# PROC106B_AOP_IO.net
KiCad netlist of a schematic drawn in Altium Designer
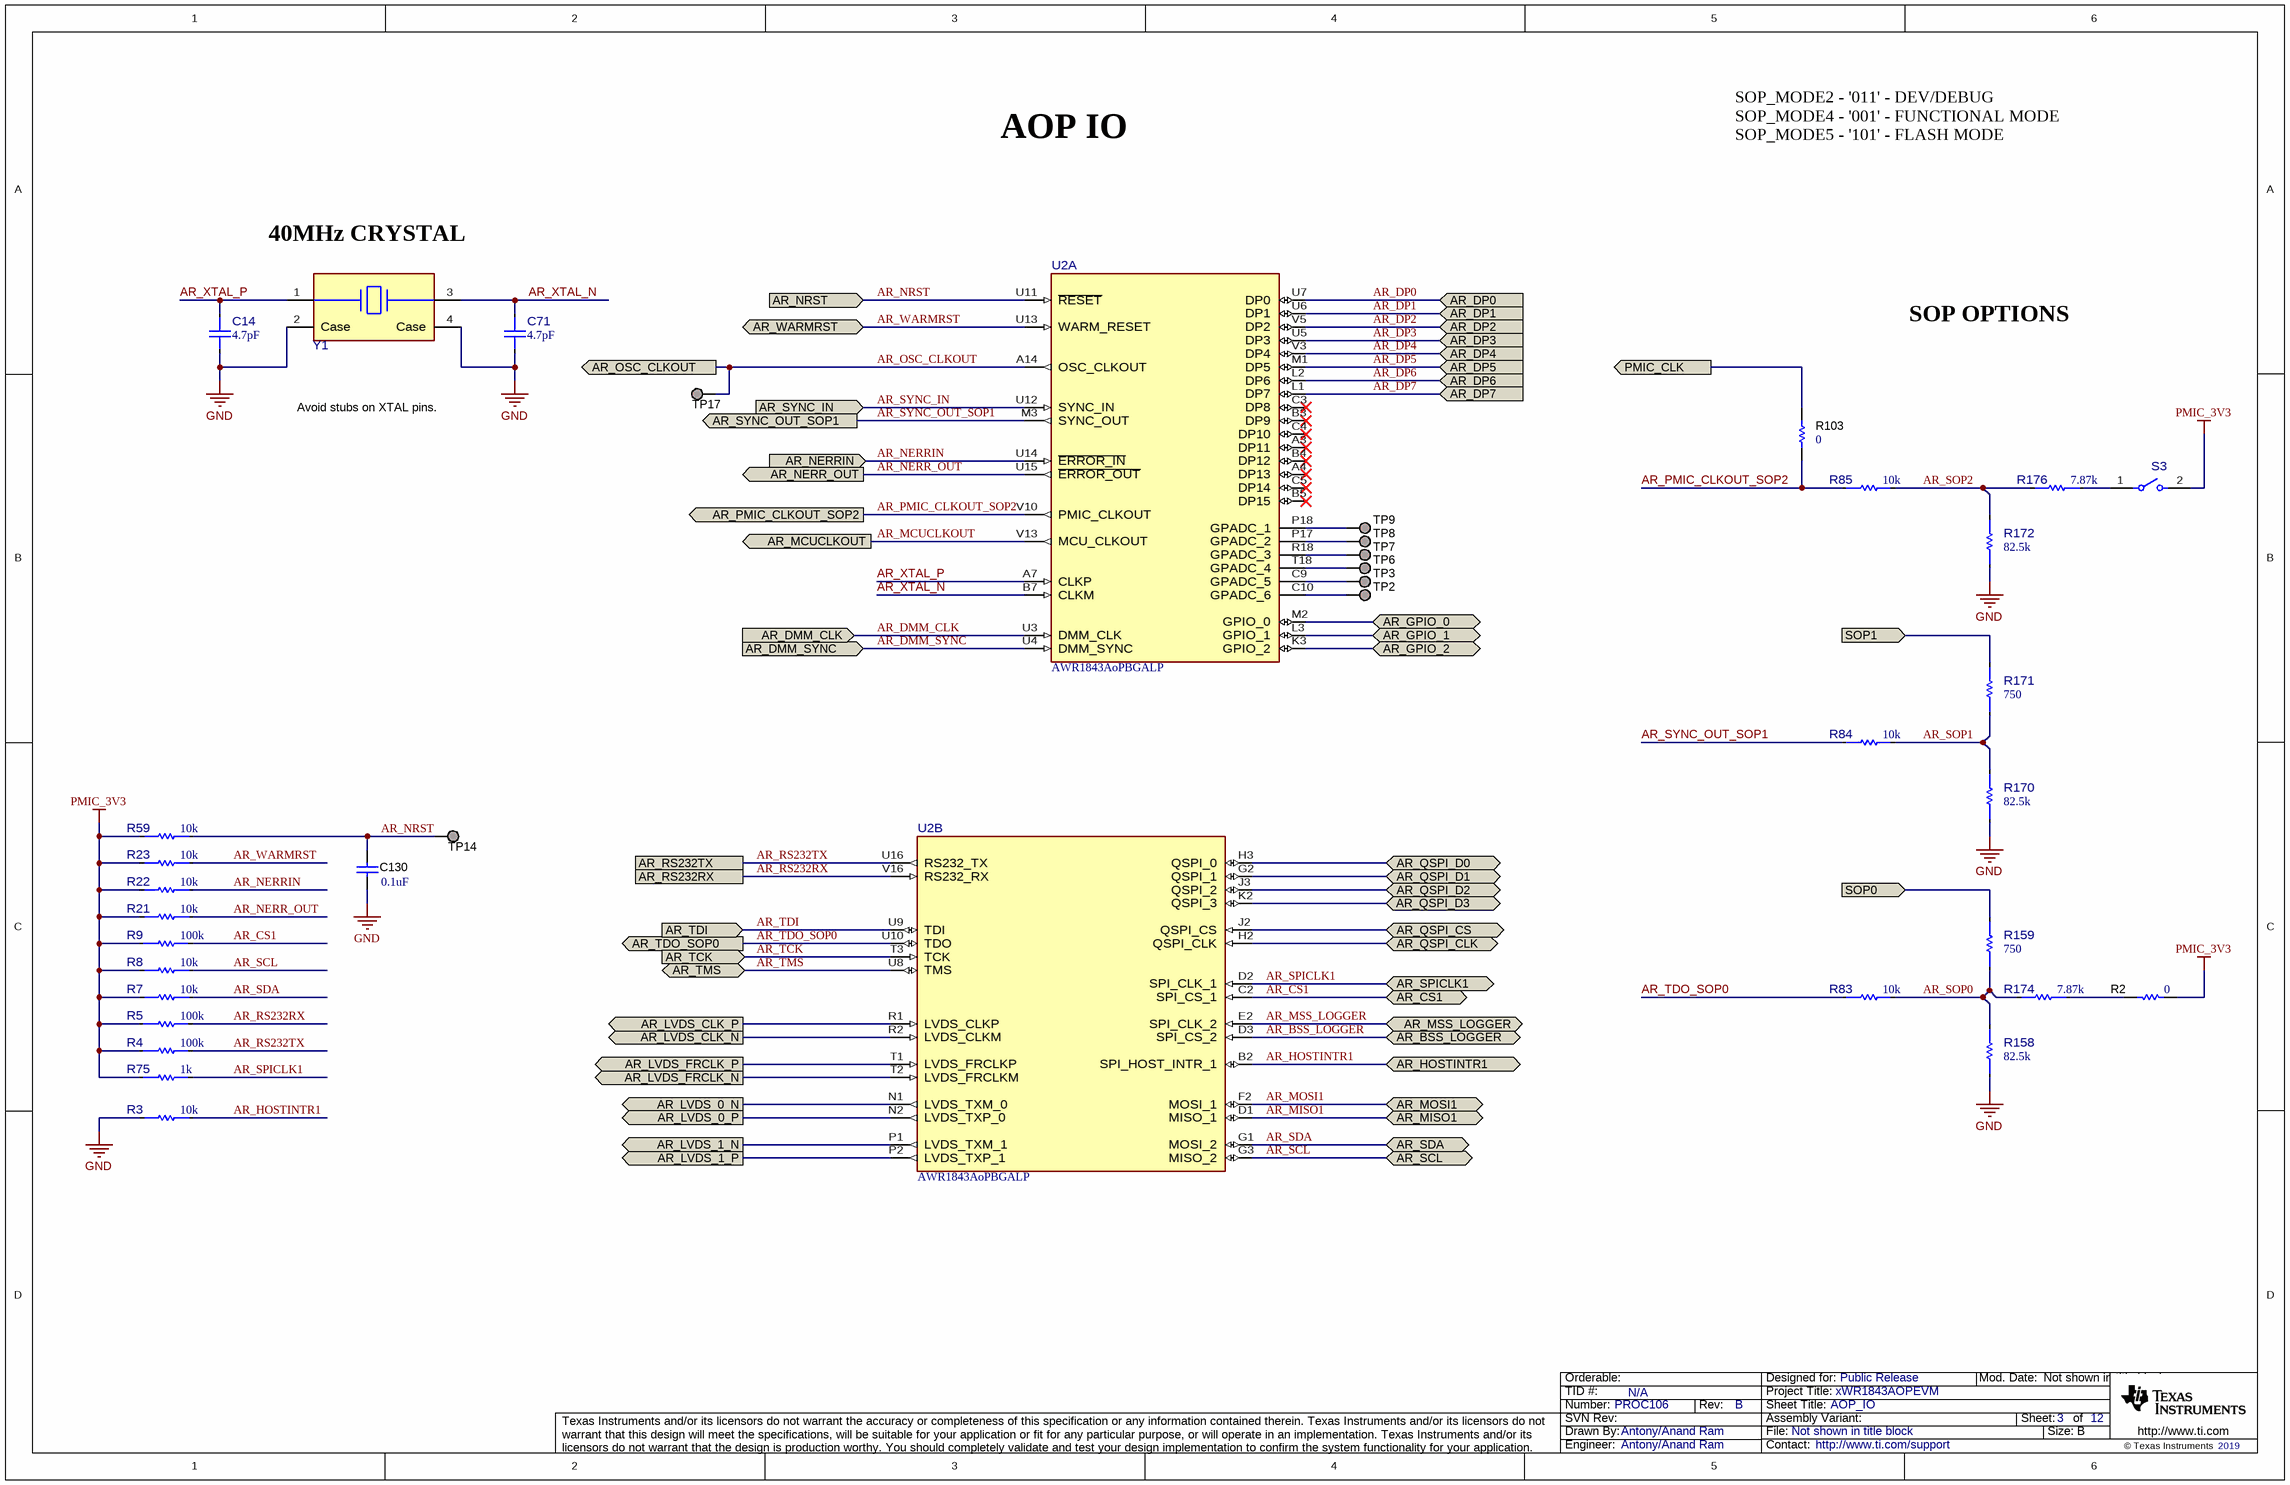
[diagram p0: PROC106B_AOP_IO.SchDoc]

(export (version "E")
  (design (tool "Eeschema 10.0.6"))
  (components
    (comp (ref "C14")
      (value "CGA1A2C0G1H4R7C030BA")
      (footprint "FP-CGA1A2C0G1H4R7C030BA_0201-IPC_C")
      (description "Cap Ceramic 4.7pF 50V C0G 0.25pF Pad SMD 0201 125°C Automotive T/R")
      (fields (field (name "MANUFACTURER") "TDK") (field (name "VALUEDISPLAYED") "4.7pF"))
      (libsource (lib "Altium Vault - TI") (part "SYM-CGA1A2C0G1H4R7C030BA"))
    )
    (comp (ref "C71")
      (value "CGA1A2C0G1H4R7C030BA")
      (footprint "FP-CGA1A2C0G1H4R7C030BA_0201-IPC_C")
      (description "Cap Ceramic 4.7pF 50V C0G 0.25pF Pad SMD 0201 125°C Automotive T/R")
      (fields (field (name "MANUFACTURER") "TDK") (field (name "VALUEDISPLAYED") "4.7pF"))
      (libsource (lib "Altium Vault - TI") (part "SYM-CGA1A2C0G1H4R7C030BA"))
    )
    (comp (ref "C130")
      (value "GCM155R71C104KA55D")
      (footprint "0402L")
      (description "CAP, CERM, 0.1 uF, 16 V, +/- 10%, X7R, 0402")
      (fields
        (field (name "MANUFACTURER") "MuRata")
        (field (name "VALUEDISPLAYED") "0.1uF")
        (field (name "PUBLISHER") "Texas Instruments")
      )
      (libsource (lib "Altium Vault - TI") (part "Capacitor"))
    )
    (comp (ref "R2")
      (value "ERJ-1GN0R00C")
      (footprint "0201L")
      (description "RES, 0, 5%, .05 W, AEC-Q200 Grade 0, 0201")
      (fields
        (field (name "MANUFACTURER") "Panasonic")
        (field (name "VALUEDISPLAYED") "0")
        (field (name "PUBLISHER") "Texas Instruments")
      )
      (libsource (lib "Altium Vault - TI") (part "Resistor"))
    )
    (comp (ref "R3")
      (value "10k")
      (footprint "FP-ERA-1AEB103C_0201-IPC_C")
      (description "RES SMD 10K OHM 0.1% 1/20W 0201")
      (fields (field (name "MANUFACTURER") "Panasonic") (field (name "PARTNUMBER") "ERA-1AEB103C"))
      (libsource (lib "Altium Vault - TI") (part "SYM-ERA-1AEB103C"))
    )
    (comp (ref "R4")
      (value "100k")
      (footprint "FP-ERJ-1GNF1003C_0201-IPC_C")
      (description "100 kOhms ±1% 0.05W, 1/20W Chip Resistor 0201 (0603 Metric) Automotive AEC-Q200 Thick Film")
      (fields
        (field (name "MANUFACTURER") "Panasonic Electronic Components")
        (field (name "PARTNUMBER") "ERJ-1GNF1003C")
      )
      (libsource (lib "Altium Vault - TI") (part "SYM-ERJ-1GNF1003C"))
    )
    (comp (ref "R5")
      (value "100k")
      (footprint "FP-ERJ-1GNF1003C_0201-IPC_C")
      (description "100 kOhms ±1% 0.05W, 1/20W Chip Resistor 0201 (0603 Metric) Automotive AEC-Q200 Thick Film")
      (fields
        (field (name "MANUFACTURER") "Panasonic Electronic Components")
        (field (name "PARTNUMBER") "ERJ-1GNF1003C")
      )
      (libsource (lib "Altium Vault - TI") (part "SYM-ERJ-1GNF1003C"))
    )
    (comp (ref "R7")
      (value "10k")
      (footprint "FP-ERA-1AEB103C_0201-IPC_C")
      (description "RES SMD 10K OHM 0.1% 1/20W 0201")
      (fields (field (name "MANUFACTURER") "Panasonic") (field (name "PARTNUMBER") "ERA-1AEB103C"))
      (libsource (lib "Altium Vault - TI") (part "SYM-ERA-1AEB103C"))
    )
    (comp (ref "R8")
      (value "10k")
      (footprint "FP-ERA-1AEB103C_0201-IPC_C")
      (description "RES SMD 10K OHM 0.1% 1/20W 0201")
      (fields (field (name "MANUFACTURER") "Panasonic") (field (name "PARTNUMBER") "ERA-1AEB103C"))
      (libsource (lib "Altium Vault - TI") (part "SYM-ERA-1AEB103C"))
    )
    (comp (ref "R9")
      (value "100k")
      (footprint "FP-ERJ-1GNF1003C_0201-IPC_C")
      (description "100 kOhms ±1% 0.05W, 1/20W Chip Resistor 0201 (0603 Metric) Automotive AEC-Q200 Thick Film")
      (fields
        (field (name "MANUFACTURER") "Panasonic Electronic Components")
        (field (name "PARTNUMBER") "ERJ-1GNF1003C")
      )
      (libsource (lib "Altium Vault - TI") (part "SYM-ERJ-1GNF1003C"))
    )
    (comp (ref "R21")
      (value "10k")
      (footprint "FP-ERA-1AEB103C_0201-IPC_C")
      (description "RES SMD 10K OHM 0.1% 1/20W 0201")
      (fields (field (name "MANUFACTURER") "Panasonic") (field (name "PARTNUMBER") "ERA-1AEB103C"))
      (libsource (lib "Altium Vault - TI") (part "SYM-ERA-1AEB103C"))
    )
    (comp (ref "R22")
      (value "10k")
      (footprint "FP-ERA-1AEB103C_0201-IPC_C")
      (description "RES SMD 10K OHM 0.1% 1/20W 0201")
      (fields (field (name "MANUFACTURER") "Panasonic") (field (name "PARTNUMBER") "ERA-1AEB103C"))
      (libsource (lib "Altium Vault - TI") (part "SYM-ERA-1AEB103C"))
    )
    (comp (ref "R23")
      (value "10k")
      (footprint "FP-ERA-1AEB103C_0201-IPC_C")
      (description "RES SMD 10K OHM 0.1% 1/20W 0201")
      (fields (field (name "MANUFACTURER") "Panasonic") (field (name "PARTNUMBER") "ERA-1AEB103C"))
      (libsource (lib "Altium Vault - TI") (part "SYM-ERA-1AEB103C"))
    )
    (comp (ref "R59")
      (value "10k")
      (footprint "FP-ERA-1AEB103C_0201-IPC_C")
      (description "RES SMD 10K OHM 0.1% 1/20W 0201")
      (fields (field (name "MANUFACTURER") "Panasonic") (field (name "PARTNUMBER") "ERA-1AEB103C"))
      (libsource (lib "Altium Vault - TI") (part "SYM-ERA-1AEB103C"))
    )
    (comp (ref "R75")
      (value "1k")
      (footprint "FP-ERJ-1GNJ102C_0201-IPC_C")
      (description "1 kOhms ±5% 0.05W, 1/20W Chip Resistor 0201 (0603 Metric) Automotive AEC-Q200 Thick Film")
      (fields
        (field (name "MANUFACTURER") "Panasonic Electronic Components")
        (field (name "PARTNUMBER") "ERJ-1GNJ102C")
      )
      (libsource (lib "Altium Vault - TI") (part "SYM-ERJ-1GNJ102C"))
    )
    (comp (ref "R83")
      (value "10k")
      (footprint "FP-ERA-1AEB103C_0201-IPC_C")
      (description "RES SMD 10K OHM 0.1% 1/20W 0201")
      (fields (field (name "MANUFACTURER") "Panasonic") (field (name "PARTNUMBER") "ERA-1AEB103C"))
      (libsource (lib "Altium Vault - TI") (part "SYM-ERA-1AEB103C"))
    )
    (comp (ref "R84")
      (value "10k")
      (footprint "FP-ERA-1AEB103C_0201-IPC_C")
      (description "RES SMD 10K OHM 0.1% 1/20W 0201")
      (fields (field (name "MANUFACTURER") "Panasonic") (field (name "PARTNUMBER") "ERA-1AEB103C"))
      (libsource (lib "Altium Vault - TI") (part "SYM-ERA-1AEB103C"))
    )
    (comp (ref "R85")
      (value "10k")
      (footprint "FP-ERA-1AEB103C_0201-IPC_C")
      (description "RES SMD 10K OHM 0.1% 1/20W 0201")
      (fields (field (name "MANUFACTURER") "Panasonic") (field (name "PARTNUMBER") "ERA-1AEB103C"))
      (libsource (lib "Altium Vault - TI") (part "SYM-ERA-1AEB103C"))
    )
    (comp (ref "R103")
      (value "ERJ-1GN0R00C")
      (footprint "0201L")
      (description "RES, 0, 5%, .05 W, AEC-Q200 Grade 0, 0201")
      (fields
        (field (name "MANUFACTURER") "Panasonic")
        (field (name "VALUEDISPLAYED") "0")
        (field (name "PUBLISHER") "Texas Instruments")
      )
      (libsource (lib "Altium Vault - TI") (part "Resistor"))
    )
    (comp (ref "R158")
      (value "82.5k")
      (footprint "FP-ERJ-1GNF8252C_0201-IPC_C")
      (description "Res Thick Film 0201 82.5K Ohm 1% 1/20W ±200ppm/°C Molded SMD SMD T/R")
      (fields (field (name "MANUFACTURER") "Panasonic") (field (name "PARTNUMBER") "ERJ-1GNF8252C"))
      (libsource (lib "Altium Vault - TI") (part "SYM-ERJ-1GNF8252C"))
    )
    (comp (ref "R159")
      (value "750")
      (footprint "FP-ERJ-1GNJ751C_0201-IPC_C")
      (description "Res Thick Film 0201 750 Ohm 5% 0.05W(1/20W) ±200ppm/C Pad SMD Automotive T/R")
      (fields
        (field (name "MANUFACTURER") "Panasonic Electronic Components")
        (field (name "PARTNUMBER") "ERJ-1GNJ751C")
      )
      (libsource (lib "Altium Vault - TI") (part "SYM-ERJ-1GNJ751C"))
    )
    (comp (ref "R170")
      (value "82.5k")
      (footprint "FP-ERJ-1GNF8252C_0201-IPC_C")
      (description "Res Thick Film 0201 82.5K Ohm 1% 1/20W ±200ppm/°C Molded SMD SMD T/R")
      (fields (field (name "MANUFACTURER") "Panasonic") (field (name "PARTNUMBER") "ERJ-1GNF8252C"))
      (libsource (lib "Altium Vault - TI") (part "SYM-ERJ-1GNF8252C"))
    )
    (comp (ref "R171")
      (value "750")
      (footprint "FP-ERJ-1GNJ751C_0201-IPC_C")
      (description "Res Thick Film 0201 750 Ohm 5% 0.05W(1/20W) ±200ppm/C Pad SMD Automotive T/R")
      (fields
        (field (name "MANUFACTURER") "Panasonic Electronic Components")
        (field (name "PARTNUMBER") "ERJ-1GNJ751C")
      )
      (libsource (lib "Altium Vault - TI") (part "SYM-ERJ-1GNJ751C"))
    )
    (comp (ref "R172")
      (value "82.5k")
      (footprint "FP-ERJ-1GNF8252C_0201-IPC_C")
      (description "Res Thick Film 0201 82.5K Ohm 1% 1/20W ±200ppm/°C Molded SMD SMD T/R")
      (fields (field (name "MANUFACTURER") "Panasonic") (field (name "PARTNUMBER") "ERJ-1GNF8252C"))
      (libsource (lib "Altium Vault - TI") (part "SYM-ERJ-1GNF8252C"))
    )
    (comp (ref "R174")
      (value "7.87k")
      (footprint "FP-ERJ-1GNF7871C_0201-IPC_C")
      (description "Res Thick Film 0201 7.87K Ohm 1% 1/20W ±200ppm/°C Molded SMD SMD T/R")
      (fields (field (name "MANUFACTURER") "Panasonic") (field (name "PARTNUMBER") "ERJ-1GNF7871C"))
      (libsource (lib "Altium Vault - TI") (part "SYM-ERJ-1GNF7871C"))
    )
    (comp (ref "R176")
      (value "7.87k")
      (footprint "FP-ERJ-1GNF7871C_0201-IPC_C")
      (description "Res Thick Film 0201 7.87K Ohm 1% 1/20W ±200ppm/°C Molded SMD SMD T/R")
      (fields (field (name "MANUFACTURER") "Panasonic") (field (name "PARTNUMBER") "ERJ-1GNF7871C"))
      (libsource (lib "Altium Vault - TI") (part "SYM-ERJ-1GNF7871C"))
    )
    (comp (ref "S3")
      (value "CHS-01TA")
      (footprint "FP-CHS-01TA_SMT_SW_5MM4_2MM5-MFG")
      (description "SWITCH SLIDE DIP SPST 100MA 6V")
      (fields (field (name "MANUFACTURER") "Nidec Copal Electronics"))
      (libsource (lib "Altium Vault - TI") (part "SYM-PTS635SK25SM"))
    )
    (comp (ref "TP2")
      (value "TESTPOINT")
      (footprint "TP_25MIL-SMT")
      (description "TEST POINT.  No entry in BOM.")
      (libsource (lib "Altium Vault - TI") (part "TESTPOINT"))
    )
    (comp (ref "TP3")
      (value "TESTPOINT")
      (footprint "TP_25MIL-SMT")
      (description "TEST POINT.  No entry in BOM.")
      (libsource (lib "Altium Vault - TI") (part "TESTPOINT"))
    )
    (comp (ref "TP6")
      (value "TESTPOINT")
      (footprint "TP_25MIL-SMT")
      (description "TEST POINT.  No entry in BOM.")
      (libsource (lib "Altium Vault - TI") (part "TESTPOINT"))
    )
    (comp (ref "TP7")
      (value "TESTPOINT")
      (footprint "TP_25MIL-SMT")
      (description "TEST POINT.  No entry in BOM.")
      (libsource (lib "Altium Vault - TI") (part "TESTPOINT"))
    )
    (comp (ref "TP8")
      (value "TESTPOINT")
      (footprint "TP_25MIL-SMT")
      (description "TEST POINT.  No entry in BOM.")
      (libsource (lib "Altium Vault - TI") (part "TESTPOINT"))
    )
    (comp (ref "TP9")
      (value "TESTPOINT")
      (footprint "TP_25MIL-SMT")
      (description "TEST POINT.  No entry in BOM.")
      (libsource (lib "Altium Vault - TI") (part "TESTPOINT"))
    )
    (comp (ref "TP14")
      (value "TESTPOINT")
      (footprint "TP_25MIL-SMT")
      (description "TEST POINT.  No entry in BOM.")
      (libsource (lib "Altium Vault - TI") (part "TESTPOINT"))
    )
    (comp (ref "TP17")
      (value "TESTPOINT")
      (footprint "TP_25MIL-SMT")
      (description "TEST POINT.  No entry in BOM.")
      (libsource (lib "Altium Vault - TI") (part "TESTPOINT"))
    )
    (comp (ref "U2")
      (value "AWR1843AoPBGALP")
      (footprint "ALP0180A-MFG")
      (fields (field (name "MANUFACTURER") "Texas Instruments") (field (name "PARTNUMBER") "AWR1843AoPBGALP"))
      (libsource (lib "Altium Vault - TI") (part "SYM-AWR1843AoPBGALP"))
    )
    (comp (ref "Y1")
      (value "FW4000044Q")
      (footprint "FP-FW4000044Q_4-SMD-2.0x1.6mm-MFG")
      (description "40MHz ±10ppm Crystal 8pF 50 Ohms 4-SMD, No Lead")
      (fields (field (name "MANUFACTURER") "Diodes") (field (name "DIGIKEY PART NUMBER") "FW4000044QDICT-ND"))
      (libsource (lib "Altium Vault - TI") (part "SYM-FW4000044Q"))
    )
  )
  (nets
    (net (code "1") (name "/AR_BSS_LOGGER") (class "Default")
      (node (ref "U2") (pin "D3") (pinfunction "SPI_CS_2_D3") (pintype "input"))
    )
    (net (code "2") (name "/AR_CS1") (class "Default")
      (node (ref "R9") (pin "2") (pinfunction "2_2") (pintype "passive"))
      (node (ref "U2") (pin "C2") (pinfunction "SPI_CS_1_C2") (pintype "input"))
    )
    (net (code "3") (name "/AR_DMM_CLK") (class "Default")
      (node (ref "U2") (pin "U3") (pinfunction "DMM_CLK_U3") (pintype "input"))
    )
    (net (code "4") (name "/AR_DMM_SYNC") (class "Default")
      (node (ref "U2") (pin "U4") (pinfunction "DMM_SYNC_U4") (pintype "input"))
    )
    (net (code "5") (name "/AR_DP0") (class "Default")
      (node (ref "U2") (pin "U7") (pinfunction "DP0_U7") (pintype "bidirectional"))
    )
    (net (code "6") (name "/AR_DP1") (class "Default")
      (node (ref "U2") (pin "U6") (pinfunction "DP1_U6") (pintype "bidirectional"))
    )
    (net (code "7") (name "/AR_DP2") (class "Default")
      (node (ref "U2") (pin "V5") (pinfunction "DP2_V5") (pintype "bidirectional"))
    )
    (net (code "8") (name "/AR_DP3") (class "Default")
      (node (ref "U2") (pin "U5") (pinfunction "DP3_U5") (pintype "bidirectional"))
    )
    (net (code "9") (name "/AR_DP4") (class "Default")
      (node (ref "U2") (pin "V3") (pinfunction "DP4_V3") (pintype "bidirectional"))
    )
    (net (code "10") (name "/AR_DP5") (class "Default")
      (node (ref "U2") (pin "M1") (pinfunction "DP5_M1") (pintype "bidirectional"))
    )
    (net (code "11") (name "/AR_DP6") (class "Default")
      (node (ref "U2") (pin "L2") (pinfunction "DP6_L2") (pintype "bidirectional"))
    )
    (net (code "12") (name "/AR_DP7") (class "Default")
      (node (ref "U2") (pin "L1") (pinfunction "DP7_L1") (pintype "bidirectional"))
    )
    (net (code "13") (name "/AR_GPIO_0") (class "Default")
      (node (ref "U2") (pin "M2") (pinfunction "GPIO_0_M2") (pintype "bidirectional"))
    )
    (net (code "14") (name "/AR_GPIO_1") (class "Default")
      (node (ref "U2") (pin "L3") (pinfunction "GPIO_1_L3") (pintype "bidirectional"))
    )
    (net (code "15") (name "/AR_GPIO_2") (class "Default")
      (node (ref "U2") (pin "K3") (pinfunction "GPIO_2_K3") (pintype "bidirectional"))
    )
    (net (code "16") (name "/AR_HOSTINTR1") (class "Default")
      (node (ref "R3") (pin "1") (pinfunction "1_1") (pintype "passive"))
      (node (ref "U2") (pin "B2") (pinfunction "SPI_HOST_INTR_1_B2") (pintype "bidirectional"))
    )
    (net (code "17") (name "/AR_LVDS_0_N") (class "Default")
      (node (ref "U2") (pin "N1") (pinfunction "LVDS_TXM_0_N1") (pintype "output"))
    )
    (net (code "18") (name "/AR_LVDS_0_P") (class "Default")
      (node (ref "U2") (pin "N2") (pinfunction "LVDS_TXP_0_N2") (pintype "output"))
    )
    (net (code "19") (name "/AR_LVDS_1_N") (class "Default")
      (node (ref "U2") (pin "P1") (pinfunction "LVDS_TXM_1_P1") (pintype "output"))
    )
    (net (code "20") (name "/AR_LVDS_1_P") (class "Default")
      (node (ref "U2") (pin "P2") (pinfunction "LVDS_TXP_1_P2") (pintype "output"))
    )
    (net (code "21") (name "/AR_LVDS_CLK_N") (class "Default")
      (node (ref "U2") (pin "R2") (pinfunction "LVDS_CLKM_R2") (pintype "input"))
    )
    (net (code "22") (name "/AR_LVDS_CLK_P") (class "Default")
      (node (ref "U2") (pin "R1") (pinfunction "LVDS_CLKP_R1") (pintype "input"))
    )
    (net (code "23") (name "/AR_LVDS_FRCLK_N") (class "Default")
      (node (ref "U2") (pin "T2") (pinfunction "LVDS_FRCLKM_T2") (pintype "input"))
    )
    (net (code "24") (name "/AR_LVDS_FRCLK_P") (class "Default")
      (node (ref "U2") (pin "T1") (pinfunction "LVDS_FRCLKP_T1") (pintype "input"))
    )
    (net (code "25") (name "/AR_MCUCLKOUT") (class "Default")
      (node (ref "U2") (pin "V13") (pinfunction "MCU_CLKOUT_V13") (pintype "output"))
    )
    (net (code "26") (name "/AR_MISO1") (class "Default")
      (node (ref "U2") (pin "D1") (pinfunction "MISO_1_D1") (pintype "bidirectional"))
    )
    (net (code "27") (name "/AR_MOSI1") (class "Default")
      (node (ref "U2") (pin "F2") (pinfunction "MOSI_1_F2") (pintype "bidirectional"))
    )
    (net (code "28") (name "/AR_MSS_LOGGER") (class "Default")
      (node (ref "U2") (pin "E2") (pinfunction "SPI_CLK_2_E2") (pintype "input"))
    )
    (net (code "29") (name "/AR_NERRIN") (class "Default")
      (node (ref "R22") (pin "1") (pinfunction "1_1") (pintype "passive"))
      (node (ref "U2") (pin "U14") (pinfunction "~{ERROR_IN}_U14") (pintype "input"))
    )
    (net (code "30") (name "/AR_NERR_OUT") (class "Default")
      (node (ref "R21") (pin "1") (pinfunction "1_1") (pintype "passive"))
      (node (ref "U2") (pin "U15") (pinfunction "~{ERROR_OUT}_U15") (pintype "output"))
    )
    (net (code "31") (name "/AR_NRST") (class "Default")
      (node (ref "C130") (pin "2") (pinfunction "2_2") (pintype "passive"))
      (node (ref "R59") (pin "1") (pinfunction "1_1") (pintype "passive"))
      (node (ref "TP14") (pin "1") (pintype "passive"))
      (node (ref "U2") (pin "U11") (pinfunction "~{RESET}_U11") (pintype "input"))
    )
    (net (code "32") (name "/AR_OSC_CLKOUT") (class "Default")
      (node (ref "TP17") (pin "1") (pintype "passive"))
      (node (ref "U2") (pin "A14") (pinfunction "OSC_CLKOUT_A14") (pintype "output"))
    )
    (net (code "33") (name "/AR_PMIC_CLKOUT_SOP2") (class "Default")
      (node (ref "R103") (pin "1") (pinfunction "1_1") (pintype "passive"))
      (node (ref "R85") (pin "1") (pinfunction "1_1") (pintype "passive"))
      (node (ref "U2") (pin "V10") (pinfunction "PMIC_CLKOUT_V10") (pintype "output"))
    )
    (net (code "34") (name "/AR_QSPI_CLK") (class "Default")
      (node (ref "U2") (pin "H2") (pinfunction "QSPI_CLK_H2") (pintype "input"))
    )
    (net (code "35") (name "/AR_QSPI_CS") (class "Default")
      (node (ref "U2") (pin "J2") (pinfunction "QSPI_CS_J2") (pintype "input"))
    )
    (net (code "36") (name "/AR_QSPI_D0") (class "Default")
      (node (ref "U2") (pin "H3") (pinfunction "QSPI_0_H3") (pintype "bidirectional"))
    )
    (net (code "37") (name "/AR_QSPI_D1") (class "Default")
      (node (ref "U2") (pin "G2") (pinfunction "QSPI_1_G2") (pintype "bidirectional"))
    )
    (net (code "38") (name "/AR_QSPI_D2") (class "Default")
      (node (ref "U2") (pin "J3") (pinfunction "QSPI_2_J3") (pintype "bidirectional"))
    )
    (net (code "39") (name "/AR_QSPI_D3") (class "Default")
      (node (ref "U2") (pin "K2") (pinfunction "QSPI_3_K2") (pintype "bidirectional"))
    )
    (net (code "40") (name "/AR_RS232RX") (class "Default")
      (node (ref "R5") (pin "2") (pinfunction "2_2") (pintype "passive"))
      (node (ref "U2") (pin "V16") (pinfunction "RS232_RX_V16") (pintype "input"))
    )
    (net (code "41") (name "/AR_RS232TX") (class "Default")
      (node (ref "R4") (pin "2") (pinfunction "2_2") (pintype "passive"))
      (node (ref "U2") (pin "U16") (pinfunction "RS232_TX_U16") (pintype "output"))
    )
    (net (code "42") (name "/AR_SCL") (class "Default")
      (node (ref "R8") (pin "1") (pinfunction "1_1") (pintype "passive"))
      (node (ref "U2") (pin "G3") (pinfunction "MISO_2_G3") (pintype "bidirectional"))
    )
    (net (code "43") (name "/AR_SDA") (class "Default")
      (node (ref "R7") (pin "1") (pinfunction "1_1") (pintype "passive"))
      (node (ref "U2") (pin "G1") (pinfunction "MOSI_2_G1") (pintype "bidirectional"))
    )
    (net (code "44") (name "/AR_SOP0") (class "Default")
      (node (ref "R158") (pin "2") (pinfunction "2_2") (pintype "passive"))
      (node (ref "R159") (pin "1") (pinfunction "1_1") (pintype "passive"))
      (node (ref "R174") (pin "2") (pinfunction "2_2") (pintype "passive"))
      (node (ref "R83") (pin "2") (pinfunction "2_2") (pintype "passive"))
    )
    (net (code "45") (name "/AR_SOP1") (class "Default")
      (node (ref "R170") (pin "2") (pinfunction "2_2") (pintype "passive"))
      (node (ref "R171") (pin "1") (pinfunction "1_1") (pintype "passive"))
      (node (ref "R84") (pin "2") (pinfunction "2_2") (pintype "passive"))
    )
    (net (code "46") (name "/AR_SOP2") (class "Default")
      (node (ref "R172") (pin "2") (pinfunction "2_2") (pintype "passive"))
      (node (ref "R176") (pin "2") (pinfunction "2_2") (pintype "passive"))
      (node (ref "R85") (pin "2") (pinfunction "2_2") (pintype "passive"))
    )
    (net (code "47") (name "/AR_SPICLK1") (class "Default")
      (node (ref "R75") (pin "2") (pinfunction "2_2") (pintype "passive"))
      (node (ref "U2") (pin "D2") (pinfunction "SPI_CLK_1_D2") (pintype "input"))
    )
    (net (code "48") (name "/AR_SYNC_IN") (class "Default")
      (node (ref "U2") (pin "U12") (pinfunction "SYNC_IN_U12") (pintype "input"))
    )
    (net (code "49") (name "/AR_SYNC_OUT_SOP1") (class "Default")
      (node (ref "R84") (pin "1") (pinfunction "1_1") (pintype "passive"))
      (node (ref "U2") (pin "M3") (pinfunction "SYNC_OUT_M3") (pintype "output"))
    )
    (net (code "50") (name "/AR_TCK") (class "Default")
      (node (ref "U2") (pin "T3") (pinfunction "TCK_T3") (pintype "input"))
    )
    (net (code "51") (name "/AR_TDI") (class "Default")
      (node (ref "U2") (pin "U9") (pinfunction "TDI_U9") (pintype "bidirectional"))
    )
    (net (code "52") (name "/AR_TDO_SOP0") (class "Default")
      (node (ref "R83") (pin "1") (pinfunction "1_1") (pintype "passive"))
      (node (ref "U2") (pin "U10") (pinfunction "TDO_U10") (pintype "bidirectional"))
    )
    (net (code "53") (name "/AR_TMS") (class "Default")
      (node (ref "U2") (pin "U8") (pinfunction "TMS_U8") (pintype "bidirectional"))
    )
    (net (code "54") (name "/AR_WARMRST") (class "Default")
      (node (ref "R23") (pin "1") (pinfunction "1_1") (pintype "passive"))
      (node (ref "U2") (pin "U13") (pinfunction "WARM_RESET_U13") (pintype "input"))
    )
    (net (code "55") (name "/AR_XTAL_N") (class "Default")
      (node (ref "C71") (pin "1") (pinfunction "1_1") (pintype "passive"))
      (node (ref "U2") (pin "B7") (pinfunction "CLKM_B7") (pintype "input"))
      (node (ref "Y1") (pin "3") (pinfunction "2_Xtal_3") (pintype "passive"))
    )
    (net (code "56") (name "/AR_XTAL_P") (class "Default")
      (node (ref "C14") (pin "1") (pinfunction "1_1") (pintype "passive"))
      (node (ref "U2") (pin "A7") (pinfunction "CLKP_A7") (pintype "input"))
      (node (ref "Y1") (pin "1") (pinfunction "1_Xtal_1") (pintype "passive"))
    )
    (net (code "57") (name "/PMIC_CLK") (class "Default")
      (node (ref "R103") (pin "2") (pinfunction "2_2") (pintype "passive"))
    )
    (net (code "58") (name "/SOP0") (class "Default")
      (node (ref "R159") (pin "2") (pinfunction "2_2") (pintype "passive"))
    )
    (net (code "59") (name "/SOP1") (class "Default")
      (node (ref "R171") (pin "2") (pinfunction "2_2") (pintype "passive"))
    )
    (net (code "60") (name "GND") (class "Default")
      (node (ref "C130") (pin "1") (pinfunction "1_1") (pintype "passive"))
      (node (ref "C14") (pin "2") (pinfunction "2_2") (pintype "passive"))
      (node (ref "C71") (pin "2") (pinfunction "2_2") (pintype "passive"))
      (node (ref "R158") (pin "1") (pinfunction "1_1") (pintype "passive"))
      (node (ref "R170") (pin "1") (pinfunction "1_1") (pintype "passive"))
      (node (ref "R172") (pin "1") (pinfunction "1_1") (pintype "passive"))
      (node (ref "R3") (pin "2") (pinfunction "2_2") (pintype "passive"))
      (node (ref "Y1") (pin "2") (pinfunction "Case_2") (pintype "passive"))
      (node (ref "Y1") (pin "4") (pinfunction "Case_4") (pintype "passive"))
    )
    (net (code "61") (name "Net-(R174-Pad1)") (class "Default")
      (node (ref "R174") (pin "1") (pinfunction "1_1") (pintype "passive"))
      (node (ref "R2") (pin "1") (pinfunction "1_1") (pintype "passive"))
    )
    (net (code "62") (name "Net-(R176-Pad1)") (class "Default")
      (node (ref "R176") (pin "1") (pinfunction "1_1") (pintype "passive"))
      (node (ref "S3") (pin "1") (pinfunction "1_1") (pintype "passive"))
    )
    (net (code "63") (name "Net-(U2A-GPADC_1)") (class "Default")
      (node (ref "TP9") (pin "1") (pintype "passive"))
      (node (ref "U2") (pin "P18") (pinfunction "GPADC_1_P18") (pintype "passive"))
    )
    (net (code "64") (name "Net-(U2A-GPADC_2)") (class "Default")
      (node (ref "TP8") (pin "1") (pintype "passive"))
      (node (ref "U2") (pin "P17") (pinfunction "GPADC_2_P17") (pintype "passive"))
    )
    (net (code "65") (name "Net-(U2A-GPADC_3)") (class "Default")
      (node (ref "TP7") (pin "1") (pintype "passive"))
      (node (ref "U2") (pin "R18") (pinfunction "GPADC_3_R18") (pintype "passive"))
    )
    (net (code "66") (name "Net-(U2A-GPADC_4)") (class "Default")
      (node (ref "TP6") (pin "1") (pintype "passive"))
      (node (ref "U2") (pin "T18") (pinfunction "GPADC_4_T18") (pintype "passive"))
    )
    (net (code "67") (name "Net-(U2A-GPADC_5)") (class "Default")
      (node (ref "TP3") (pin "1") (pintype "passive"))
      (node (ref "U2") (pin "C9") (pinfunction "GPADC_5_C9") (pintype "passive"))
    )
    (net (code "68") (name "Net-(U2A-GPADC_6)") (class "Default")
      (node (ref "TP2") (pin "1") (pintype "passive"))
      (node (ref "U2") (pin "C10") (pinfunction "GPADC_6_C10") (pintype "passive"))
    )
    (net (code "69") (name "PMIC_3V3") (class "Default")
      (node (ref "R2") (pin "2") (pinfunction "2_2") (pintype "passive"))
      (node (ref "R21") (pin "2") (pinfunction "2_2") (pintype "passive"))
      (node (ref "R22") (pin "2") (pinfunction "2_2") (pintype "passive"))
      (node (ref "R23") (pin "2") (pinfunction "2_2") (pintype "passive"))
      (node (ref "R4") (pin "1") (pinfunction "1_1") (pintype "passive"))
      (node (ref "R5") (pin "1") (pinfunction "1_1") (pintype "passive"))
      (node (ref "R59") (pin "2") (pinfunction "2_2") (pintype "passive"))
      (node (ref "R7") (pin "2") (pinfunction "2_2") (pintype "passive"))
      (node (ref "R75") (pin "1") (pinfunction "1_1") (pintype "passive"))
      (node (ref "R8") (pin "2") (pinfunction "2_2") (pintype "passive"))
      (node (ref "R9") (pin "1") (pinfunction "1_1") (pintype "passive"))
      (node (ref "S3") (pin "2") (pinfunction "2_2") (pintype "passive"))
    )
    (net (code "70") (name "unconnected-(U2A-DP8-PadC3)") (class "Default")
      (node (ref "U2") (pin "C3") (pinfunction "DP8_C3") (pintype "bidirectional+no_connect"))
    )
    (net (code "71") (name "unconnected-(U2A-DP9-PadB3)") (class "Default")
      (node (ref "U2") (pin "B3") (pinfunction "DP9_B3") (pintype "bidirectional+no_connect"))
    )
    (net (code "72") (name "unconnected-(U2A-DP10-PadC4)") (class "Default")
      (node (ref "U2") (pin "C4") (pinfunction "DP10_C4") (pintype "bidirectional+no_connect"))
    )
    (net (code "73") (name "unconnected-(U2A-DP11-PadA3)") (class "Default")
      (node (ref "U2") (pin "A3") (pinfunction "DP11_A3") (pintype "bidirectional+no_connect"))
    )
    (net (code "74") (name "unconnected-(U2A-DP12-PadB4)") (class "Default")
      (node (ref "U2") (pin "B4") (pinfunction "DP12_B4") (pintype "bidirectional+no_connect"))
    )
    (net (code "75") (name "unconnected-(U2A-DP13-PadA4)") (class "Default")
      (node (ref "U2") (pin "A4") (pinfunction "DP13_A4") (pintype "bidirectional+no_connect"))
    )
    (net (code "76") (name "unconnected-(U2A-DP14-PadC5)") (class "Default")
      (node (ref "U2") (pin "C5") (pinfunction "DP14_C5") (pintype "bidirectional+no_connect"))
    )
    (net (code "77") (name "unconnected-(U2A-DP15-PadB5)") (class "Default")
      (node (ref "U2") (pin "B5") (pinfunction "DP15_B5") (pintype "bidirectional+no_connect"))
    )
  )
)
